# opto_endstop.net
KiCad netlist of a schematic drawn in EAGLE
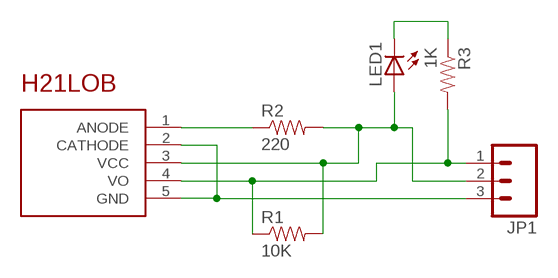
[diagram p0: schematic, sheet 1]

(export (version "E")
  (design (tool "Eeschema 10.0.6"))
  (components
    (comp (ref "JP1")
      (value "M03LONGPADS")
      (footprint "eagle-import:1X03_LONGPADS")
      (libsource (lib "eagle-import") (part "M03LONGPADS"))
    )
    (comp (ref "LED1")
      (value "LED5MM")
      (footprint "eagle-import:LED5MM")
      (libsource (lib "eagle-import") (part "LED5MM"))
    )
    (comp (ref "R1")
      (value "10K")
      (footprint "eagle-import:AXIAL-0.3")
      (libsource (lib "eagle-import") (part "RESISTORAXIAL-0.3-FRANK"))
    )
    (comp (ref "R2")
      (value "220")
      (footprint "eagle-import:AXIAL-0.3")
      (libsource (lib "eagle-import") (part "RESISTORAXIAL-0.3-FRANK"))
    )
    (comp (ref "R3")
      (value "1K")
      (footprint "eagle-import:AXIAL-0.3")
      (libsource (lib "eagle-import") (part "RESISTORAXIAL-0.3-FRANK"))
    )
    (comp (ref "U$2")
      (value "H21LOB")
      (footprint "eagle-import:H21")
      (libsource (lib "eagle-import") (part "H21LOB"))
    )
  )
  (nets
    (net (code "1") (name "Net-(LED1-C)") (class "Default")
      (node (ref "LED1") (pin "K") (pinfunction "C_K") (pintype "passive"))
      (node (ref "R3") (pin "P$1") (pinfunction "1_P$1") (pintype "passive"))
    )
    (net (code "2") (name "Net-(R1-1)") (class "Default")
      (node (ref "JP1") (pin "1") (pinfunction "1_1") (pintype "passive"))
      (node (ref "R1") (pin "P$1") (pinfunction "1_P$1") (pintype "passive"))
      (node (ref "R3") (pin "P$2") (pinfunction "2_P$2") (pintype "passive"))
      (node (ref "U$2") (pin "4") (pinfunction "VO_4") (pintype "bidirectional"))
    )
    (net (code "3") (name "Net-(R1-2)") (class "Default")
      (node (ref "JP1") (pin "2") (pinfunction "2_2") (pintype "passive"))
      (node (ref "LED1") (pin "A") (pinfunction "A_A") (pintype "passive"))
      (node (ref "R1") (pin "P$2") (pinfunction "2_P$2") (pintype "passive"))
      (node (ref "R2") (pin "P$2") (pinfunction "2_P$2") (pintype "passive"))
      (node (ref "U$2") (pin "3") (pinfunction "VCC_3") (pintype "bidirectional"))
    )
    (net (code "4") (name "Net-(R2-1)") (class "Default")
      (node (ref "R2") (pin "P$1") (pinfunction "1_P$1") (pintype "passive"))
      (node (ref "U$2") (pin "1") (pinfunction "ANODE_1") (pintype "bidirectional"))
    )
    (net (code "5") (name "Net-(U$2-CATHODE)") (class "Default")
      (node (ref "JP1") (pin "3") (pinfunction "3_3") (pintype "passive"))
      (node (ref "U$2") (pin "2") (pinfunction "CATHODE_2") (pintype "bidirectional"))
      (node (ref "U$2") (pin "5") (pinfunction "GND_5") (pintype "bidirectional"))
    )
  )
)
